# MRCS-CMRI-32-Line-stall-motor-adapter.net
KiCad netlist of a schematic drawn in EAGLE
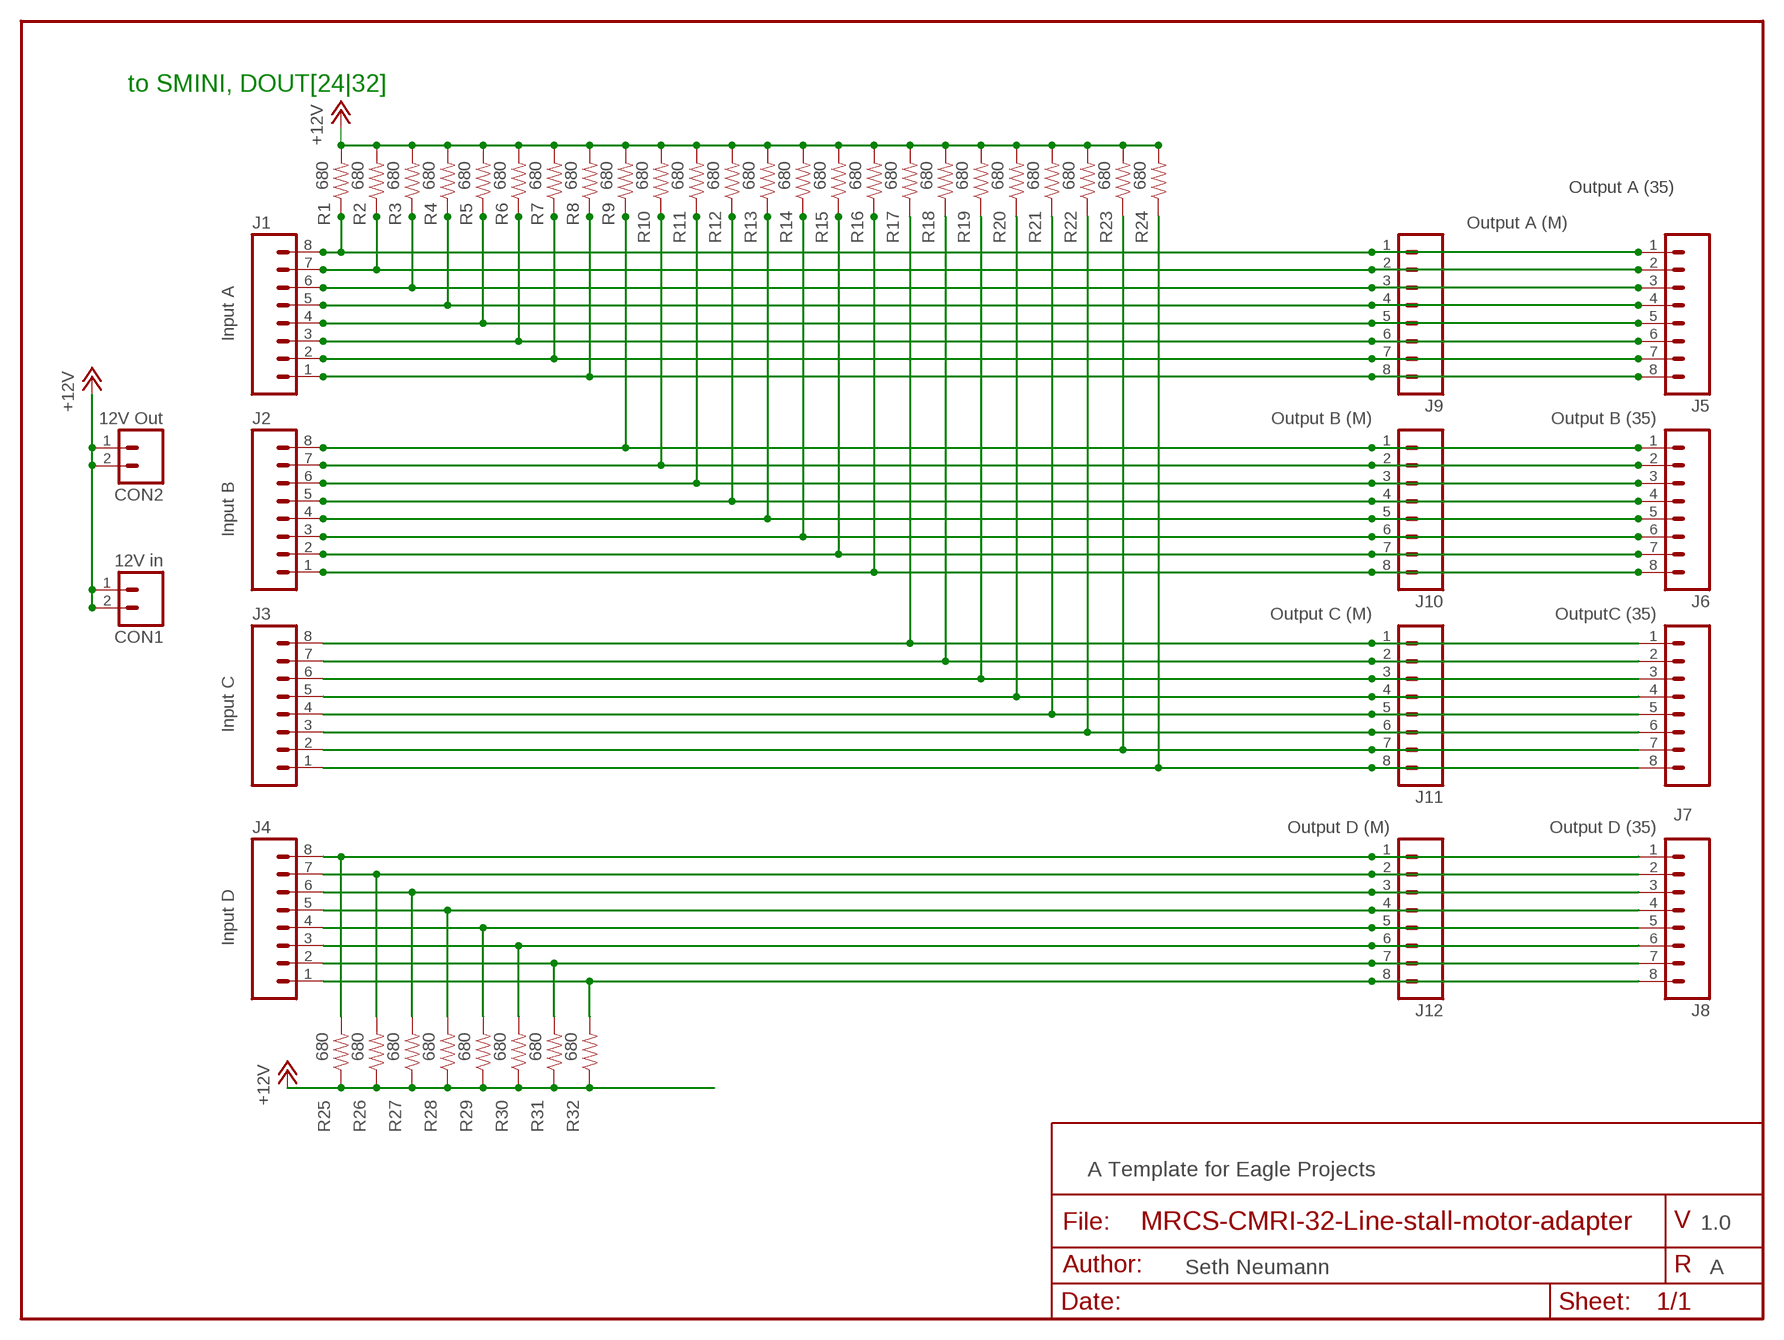
[diagram p0: schematic, sheet 1]

(export (version "E")
  (design (tool "Eeschema 10.0.6"))
  (components
    (comp (ref "CON1")
      (value "12V in")
      (footprint "eagle-import:SCREWTERMINAL-5MM-2")
      (libsource (lib "eagle-import") (part "CONNECTOR-M025MM-LOCK"))
    )
    (comp (ref "CON2")
      (value "12V Out")
      (footprint "eagle-import:SCREWTERMINAL-5MM-2")
      (libsource (lib "eagle-import") (part "CONNECTOR-M025MM-LOCK"))
    )
    (comp (ref "J1")
      (value "Input A")
      (footprint "eagle-import:KK-156-8-F")
      (libsource (lib "eagle-import") (part "CONNECTOR-M081.56-F"))
    )
    (comp (ref "J2")
      (value "Input B")
      (footprint "eagle-import:KK-156-8-F")
      (libsource (lib "eagle-import") (part "CONNECTOR-M081.56-F"))
    )
    (comp (ref "J3")
      (value "Input C")
      (footprint "eagle-import:KK-156-8-F")
      (libsource (lib "eagle-import") (part "CONNECTOR-M081.56-F"))
    )
    (comp (ref "J4")
      (value "Input D")
      (footprint "eagle-import:KK-156-8-F")
      (libsource (lib "eagle-import") (part "CONNECTOR-M081.56-F"))
    )
    (comp (ref "J5")
      (value "Output A (35)")
      (footprint "eagle-import:SCREWTERMINAL-3.5MM-8")
      (libsource (lib "eagle-import") (part "CONNECTOR-M083.5MM-8"))
    )
    (comp (ref "J6")
      (value "Output B (35)")
      (footprint "eagle-import:SCREWTERMINAL-3.5MM-8")
      (libsource (lib "eagle-import") (part "CONNECTOR-M083.5MM-8"))
    )
    (comp (ref "J7")
      (value "OutputC (35)")
      (footprint "eagle-import:SCREWTERMINAL-3.5MM-8")
      (libsource (lib "eagle-import") (part "CONNECTOR-M083.5MM-8"))
    )
    (comp (ref "J8")
      (value "Output D (35)")
      (footprint "eagle-import:SCREWTERMINAL-3.5MM-8")
      (libsource (lib "eagle-import") (part "CONNECTOR-M083.5MM-8"))
    )
    (comp (ref "J9")
      (value "Output A (M)")
      (footprint "eagle-import:KK-156-8-F")
      (libsource (lib "eagle-import") (part "CONNECTOR-M081.56-F"))
    )
    (comp (ref "J10")
      (value "Output B (M)")
      (footprint "eagle-import:KK-156-8-F")
      (libsource (lib "eagle-import") (part "CONNECTOR-M081.56-F"))
    )
    (comp (ref "J11")
      (value "Output C (M)")
      (footprint "eagle-import:KK-156-8-F")
      (libsource (lib "eagle-import") (part "CONNECTOR-M081.56-F"))
    )
    (comp (ref "J12")
      (value "Output D (M)")
      (footprint "eagle-import:KK-156-8-F")
      (libsource (lib "eagle-import") (part "CONNECTOR-M081.56-F"))
    )
    (comp (ref "R1")
      (value "680")
      (footprint "eagle-import:AXIAL-0.5")
      (libsource (lib "eagle-import") (part "RESISTORPTH-1/2W"))
    )
    (comp (ref "R2")
      (value "680")
      (footprint "eagle-import:AXIAL-0.5")
      (libsource (lib "eagle-import") (part "RESISTORPTH-1/2W"))
    )
    (comp (ref "R3")
      (value "680")
      (footprint "eagle-import:AXIAL-0.5")
      (libsource (lib "eagle-import") (part "RESISTORPTH-1/2W"))
    )
    (comp (ref "R4")
      (value "680")
      (footprint "eagle-import:AXIAL-0.5")
      (libsource (lib "eagle-import") (part "RESISTORPTH-1/2W"))
    )
    (comp (ref "R5")
      (value "680")
      (footprint "eagle-import:AXIAL-0.5")
      (libsource (lib "eagle-import") (part "RESISTORPTH-1/2W"))
    )
    (comp (ref "R6")
      (value "680")
      (footprint "eagle-import:AXIAL-0.5")
      (libsource (lib "eagle-import") (part "RESISTORPTH-1/2W"))
    )
    (comp (ref "R7")
      (value "680")
      (footprint "eagle-import:AXIAL-0.5")
      (libsource (lib "eagle-import") (part "RESISTORPTH-1/2W"))
    )
    (comp (ref "R8")
      (value "680")
      (footprint "eagle-import:AXIAL-0.5")
      (libsource (lib "eagle-import") (part "RESISTORPTH-1/2W"))
    )
    (comp (ref "R9")
      (value "680")
      (footprint "eagle-import:AXIAL-0.5")
      (libsource (lib "eagle-import") (part "RESISTORPTH-1/2W"))
    )
    (comp (ref "R10")
      (value "680")
      (footprint "eagle-import:AXIAL-0.5")
      (libsource (lib "eagle-import") (part "RESISTORPTH-1/2W"))
    )
    (comp (ref "R11")
      (value "680")
      (footprint "eagle-import:AXIAL-0.5")
      (libsource (lib "eagle-import") (part "RESISTORPTH-1/2W"))
    )
    (comp (ref "R12")
      (value "680")
      (footprint "eagle-import:AXIAL-0.5")
      (libsource (lib "eagle-import") (part "RESISTORPTH-1/2W"))
    )
    (comp (ref "R13")
      (value "680")
      (footprint "eagle-import:AXIAL-0.5")
      (libsource (lib "eagle-import") (part "RESISTORPTH-1/2W"))
    )
    (comp (ref "R14")
      (value "680")
      (footprint "eagle-import:AXIAL-0.5")
      (libsource (lib "eagle-import") (part "RESISTORPTH-1/2W"))
    )
    (comp (ref "R15")
      (value "680")
      (footprint "eagle-import:AXIAL-0.5")
      (libsource (lib "eagle-import") (part "RESISTORPTH-1/2W"))
    )
    (comp (ref "R16")
      (value "680")
      (footprint "eagle-import:AXIAL-0.5")
      (libsource (lib "eagle-import") (part "RESISTORPTH-1/2W"))
    )
    (comp (ref "R17")
      (value "680")
      (footprint "eagle-import:AXIAL-0.5")
      (libsource (lib "eagle-import") (part "RESISTORPTH-1/2W"))
    )
    (comp (ref "R18")
      (value "680")
      (footprint "eagle-import:AXIAL-0.5")
      (libsource (lib "eagle-import") (part "RESISTORPTH-1/2W"))
    )
    (comp (ref "R19")
      (value "680")
      (footprint "eagle-import:AXIAL-0.5")
      (libsource (lib "eagle-import") (part "RESISTORPTH-1/2W"))
    )
    (comp (ref "R20")
      (value "680")
      (footprint "eagle-import:AXIAL-0.5")
      (libsource (lib "eagle-import") (part "RESISTORPTH-1/2W"))
    )
    (comp (ref "R21")
      (value "680")
      (footprint "eagle-import:AXIAL-0.5")
      (libsource (lib "eagle-import") (part "RESISTORPTH-1/2W"))
    )
    (comp (ref "R22")
      (value "680")
      (footprint "eagle-import:AXIAL-0.5")
      (libsource (lib "eagle-import") (part "RESISTORPTH-1/2W"))
    )
    (comp (ref "R23")
      (value "680")
      (footprint "eagle-import:AXIAL-0.5")
      (libsource (lib "eagle-import") (part "RESISTORPTH-1/2W"))
    )
    (comp (ref "R24")
      (value "680")
      (footprint "eagle-import:AXIAL-0.5")
      (libsource (lib "eagle-import") (part "RESISTORPTH-1/2W"))
    )
    (comp (ref "R25")
      (value "680")
      (footprint "eagle-import:AXIAL-0.5")
      (libsource (lib "eagle-import") (part "RESISTORPTH-1/2W"))
    )
    (comp (ref "R26")
      (value "680")
      (footprint "eagle-import:AXIAL-0.5")
      (libsource (lib "eagle-import") (part "RESISTORPTH-1/2W"))
    )
    (comp (ref "R27")
      (value "680")
      (footprint "eagle-import:AXIAL-0.5")
      (libsource (lib "eagle-import") (part "RESISTORPTH-1/2W"))
    )
    (comp (ref "R28")
      (value "680")
      (footprint "eagle-import:AXIAL-0.5")
      (libsource (lib "eagle-import") (part "RESISTORPTH-1/2W"))
    )
    (comp (ref "R29")
      (value "680")
      (footprint "eagle-import:AXIAL-0.5")
      (libsource (lib "eagle-import") (part "RESISTORPTH-1/2W"))
    )
    (comp (ref "R30")
      (value "680")
      (footprint "eagle-import:AXIAL-0.5")
      (libsource (lib "eagle-import") (part "RESISTORPTH-1/2W"))
    )
    (comp (ref "R31")
      (value "680")
      (footprint "eagle-import:AXIAL-0.5")
      (libsource (lib "eagle-import") (part "RESISTORPTH-1/2W"))
    )
    (comp (ref "R32")
      (value "680")
      (footprint "eagle-import:AXIAL-0.5")
      (libsource (lib "eagle-import") (part "RESISTORPTH-1/2W"))
    )
  )
  (nets
    (net (code "1") (name "+12V") (class "Default")
      (node (ref "CON1") (pin "1") (pinfunction "A_1") (pintype "passive"))
      (node (ref "CON1") (pin "2") (pinfunction "B_2") (pintype "passive"))
      (node (ref "CON2") (pin "1") (pinfunction "A_1") (pintype "passive"))
      (node (ref "CON2") (pin "2") (pinfunction "B_2") (pintype "passive"))
      (node (ref "R1") (pin "P$2") (pinfunction "2_P$2") (pintype "passive"))
      (node (ref "R10") (pin "P$2") (pinfunction "2_P$2") (pintype "passive"))
      (node (ref "R11") (pin "P$2") (pinfunction "2_P$2") (pintype "passive"))
      (node (ref "R12") (pin "P$2") (pinfunction "2_P$2") (pintype "passive"))
      (node (ref "R13") (pin "P$2") (pinfunction "2_P$2") (pintype "passive"))
      (node (ref "R14") (pin "P$2") (pinfunction "2_P$2") (pintype "passive"))
      (node (ref "R15") (pin "P$2") (pinfunction "2_P$2") (pintype "passive"))
      (node (ref "R16") (pin "P$2") (pinfunction "2_P$2") (pintype "passive"))
      (node (ref "R17") (pin "P$2") (pinfunction "2_P$2") (pintype "passive"))
      (node (ref "R18") (pin "P$2") (pinfunction "2_P$2") (pintype "passive"))
      (node (ref "R19") (pin "P$2") (pinfunction "2_P$2") (pintype "passive"))
      (node (ref "R2") (pin "P$2") (pinfunction "2_P$2") (pintype "passive"))
      (node (ref "R20") (pin "P$2") (pinfunction "2_P$2") (pintype "passive"))
      (node (ref "R21") (pin "P$2") (pinfunction "2_P$2") (pintype "passive"))
      (node (ref "R22") (pin "P$2") (pinfunction "2_P$2") (pintype "passive"))
      (node (ref "R23") (pin "P$2") (pinfunction "2_P$2") (pintype "passive"))
      (node (ref "R24") (pin "P$2") (pinfunction "2_P$2") (pintype "passive"))
      (node (ref "R25") (pin "P$1") (pinfunction "1_P$1") (pintype "passive"))
      (node (ref "R26") (pin "P$1") (pinfunction "1_P$1") (pintype "passive"))
      (node (ref "R27") (pin "P$1") (pinfunction "1_P$1") (pintype "passive"))
      (node (ref "R28") (pin "P$1") (pinfunction "1_P$1") (pintype "passive"))
      (node (ref "R29") (pin "P$1") (pinfunction "1_P$1") (pintype "passive"))
      (node (ref "R3") (pin "P$2") (pinfunction "2_P$2") (pintype "passive"))
      (node (ref "R30") (pin "P$1") (pinfunction "1_P$1") (pintype "passive"))
      (node (ref "R31") (pin "P$1") (pinfunction "1_P$1") (pintype "passive"))
      (node (ref "R32") (pin "P$1") (pinfunction "1_P$1") (pintype "passive"))
      (node (ref "R4") (pin "P$2") (pinfunction "2_P$2") (pintype "passive"))
      (node (ref "R5") (pin "P$2") (pinfunction "2_P$2") (pintype "passive"))
      (node (ref "R6") (pin "P$2") (pinfunction "2_P$2") (pintype "passive"))
      (node (ref "R7") (pin "P$2") (pinfunction "2_P$2") (pintype "passive"))
      (node (ref "R8") (pin "P$2") (pinfunction "2_P$2") (pintype "passive"))
      (node (ref "R9") (pin "P$2") (pinfunction "2_P$2") (pintype "passive"))
    )
    (net (code "2") (name "Net-(R1-1)") (class "Default")
      (node (ref "J1") (pin "8") (pinfunction "8_8") (pintype "passive"))
      (node (ref "J5") (pin "1") (pinfunction "1_1") (pintype "passive"))
      (node (ref "J9") (pin "1") (pinfunction "1_1") (pintype "passive"))
      (node (ref "R1") (pin "P$1") (pinfunction "1_P$1") (pintype "passive"))
    )
    (net (code "3") (name "Net-(R2-1)") (class "Default")
      (node (ref "J1") (pin "7") (pinfunction "7_7") (pintype "passive"))
      (node (ref "J5") (pin "2") (pinfunction "2_2") (pintype "passive"))
      (node (ref "J9") (pin "2") (pinfunction "2_2") (pintype "passive"))
      (node (ref "R2") (pin "P$1") (pinfunction "1_P$1") (pintype "passive"))
    )
    (net (code "4") (name "Net-(R3-1)") (class "Default")
      (node (ref "J1") (pin "6") (pinfunction "6_6") (pintype "passive"))
      (node (ref "J5") (pin "3") (pinfunction "3_3") (pintype "passive"))
      (node (ref "J9") (pin "3") (pinfunction "3_3") (pintype "passive"))
      (node (ref "R3") (pin "P$1") (pinfunction "1_P$1") (pintype "passive"))
    )
    (net (code "5") (name "Net-(R4-1)") (class "Default")
      (node (ref "J1") (pin "5") (pinfunction "5_5") (pintype "passive"))
      (node (ref "J5") (pin "4") (pinfunction "4_4") (pintype "passive"))
      (node (ref "J9") (pin "4") (pinfunction "4_4") (pintype "passive"))
      (node (ref "R4") (pin "P$1") (pinfunction "1_P$1") (pintype "passive"))
    )
    (net (code "6") (name "Net-(R5-1)") (class "Default")
      (node (ref "J1") (pin "4") (pinfunction "4_4") (pintype "passive"))
      (node (ref "J5") (pin "5") (pinfunction "5_5") (pintype "passive"))
      (node (ref "J9") (pin "5") (pinfunction "5_5") (pintype "passive"))
      (node (ref "R5") (pin "P$1") (pinfunction "1_P$1") (pintype "passive"))
    )
    (net (code "7") (name "Net-(R6-1)") (class "Default")
      (node (ref "J1") (pin "3") (pinfunction "3_3") (pintype "passive"))
      (node (ref "J5") (pin "6") (pinfunction "6_6") (pintype "passive"))
      (node (ref "J9") (pin "6") (pinfunction "6_6") (pintype "passive"))
      (node (ref "R6") (pin "P$1") (pinfunction "1_P$1") (pintype "passive"))
    )
    (net (code "8") (name "Net-(R7-1)") (class "Default")
      (node (ref "J1") (pin "2") (pinfunction "2_2") (pintype "passive"))
      (node (ref "J5") (pin "7") (pinfunction "7_7") (pintype "passive"))
      (node (ref "J9") (pin "7") (pinfunction "7_7") (pintype "passive"))
      (node (ref "R7") (pin "P$1") (pinfunction "1_P$1") (pintype "passive"))
    )
    (net (code "9") (name "Net-(R8-1)") (class "Default")
      (node (ref "J1") (pin "1") (pinfunction "1_1") (pintype "passive"))
      (node (ref "J5") (pin "8") (pinfunction "8_8") (pintype "passive"))
      (node (ref "J9") (pin "8") (pinfunction "8_8") (pintype "passive"))
      (node (ref "R8") (pin "P$1") (pinfunction "1_P$1") (pintype "passive"))
    )
    (net (code "10") (name "Net-(R9-1)") (class "Default")
      (node (ref "J10") (pin "1") (pinfunction "1_1") (pintype "passive"))
      (node (ref "J2") (pin "8") (pinfunction "8_8") (pintype "passive"))
      (node (ref "J6") (pin "1") (pinfunction "1_1") (pintype "passive"))
      (node (ref "R9") (pin "P$1") (pinfunction "1_P$1") (pintype "passive"))
    )
    (net (code "11") (name "Net-(R10-1)") (class "Default")
      (node (ref "J10") (pin "2") (pinfunction "2_2") (pintype "passive"))
      (node (ref "J2") (pin "7") (pinfunction "7_7") (pintype "passive"))
      (node (ref "J6") (pin "2") (pinfunction "2_2") (pintype "passive"))
      (node (ref "R10") (pin "P$1") (pinfunction "1_P$1") (pintype "passive"))
    )
    (net (code "12") (name "Net-(R11-1)") (class "Default")
      (node (ref "J10") (pin "3") (pinfunction "3_3") (pintype "passive"))
      (node (ref "J2") (pin "6") (pinfunction "6_6") (pintype "passive"))
      (node (ref "J6") (pin "3") (pinfunction "3_3") (pintype "passive"))
      (node (ref "R11") (pin "P$1") (pinfunction "1_P$1") (pintype "passive"))
    )
    (net (code "13") (name "Net-(R12-1)") (class "Default")
      (node (ref "J10") (pin "4") (pinfunction "4_4") (pintype "passive"))
      (node (ref "J2") (pin "5") (pinfunction "5_5") (pintype "passive"))
      (node (ref "J6") (pin "4") (pinfunction "4_4") (pintype "passive"))
      (node (ref "R12") (pin "P$1") (pinfunction "1_P$1") (pintype "passive"))
    )
    (net (code "14") (name "Net-(R13-1)") (class "Default")
      (node (ref "J10") (pin "5") (pinfunction "5_5") (pintype "passive"))
      (node (ref "J2") (pin "4") (pinfunction "4_4") (pintype "passive"))
      (node (ref "J6") (pin "5") (pinfunction "5_5") (pintype "passive"))
      (node (ref "R13") (pin "P$1") (pinfunction "1_P$1") (pintype "passive"))
    )
    (net (code "15") (name "Net-(R14-1)") (class "Default")
      (node (ref "J10") (pin "6") (pinfunction "6_6") (pintype "passive"))
      (node (ref "J2") (pin "3") (pinfunction "3_3") (pintype "passive"))
      (node (ref "J6") (pin "6") (pinfunction "6_6") (pintype "passive"))
      (node (ref "R14") (pin "P$1") (pinfunction "1_P$1") (pintype "passive"))
    )
    (net (code "16") (name "Net-(R15-1)") (class "Default")
      (node (ref "J10") (pin "7") (pinfunction "7_7") (pintype "passive"))
      (node (ref "J2") (pin "2") (pinfunction "2_2") (pintype "passive"))
      (node (ref "J6") (pin "7") (pinfunction "7_7") (pintype "passive"))
      (node (ref "R15") (pin "P$1") (pinfunction "1_P$1") (pintype "passive"))
    )
    (net (code "17") (name "Net-(R16-1)") (class "Default")
      (node (ref "J10") (pin "8") (pinfunction "8_8") (pintype "passive"))
      (node (ref "J2") (pin "1") (pinfunction "1_1") (pintype "passive"))
      (node (ref "J6") (pin "8") (pinfunction "8_8") (pintype "passive"))
      (node (ref "R16") (pin "P$1") (pinfunction "1_P$1") (pintype "passive"))
    )
    (net (code "18") (name "Net-(R17-1)") (class "Default")
      (node (ref "J11") (pin "1") (pinfunction "1_1") (pintype "passive"))
      (node (ref "J3") (pin "8") (pinfunction "8_8") (pintype "passive"))
      (node (ref "J7") (pin "1") (pinfunction "1_1") (pintype "passive"))
      (node (ref "R17") (pin "P$1") (pinfunction "1_P$1") (pintype "passive"))
    )
    (net (code "19") (name "Net-(R18-1)") (class "Default")
      (node (ref "J11") (pin "2") (pinfunction "2_2") (pintype "passive"))
      (node (ref "J3") (pin "7") (pinfunction "7_7") (pintype "passive"))
      (node (ref "J7") (pin "2") (pinfunction "2_2") (pintype "passive"))
      (node (ref "R18") (pin "P$1") (pinfunction "1_P$1") (pintype "passive"))
    )
    (net (code "20") (name "Net-(R19-1)") (class "Default")
      (node (ref "J11") (pin "3") (pinfunction "3_3") (pintype "passive"))
      (node (ref "J3") (pin "6") (pinfunction "6_6") (pintype "passive"))
      (node (ref "J7") (pin "3") (pinfunction "3_3") (pintype "passive"))
      (node (ref "R19") (pin "P$1") (pinfunction "1_P$1") (pintype "passive"))
    )
    (net (code "21") (name "Net-(R20-1)") (class "Default")
      (node (ref "J11") (pin "4") (pinfunction "4_4") (pintype "passive"))
      (node (ref "J3") (pin "5") (pinfunction "5_5") (pintype "passive"))
      (node (ref "J7") (pin "4") (pinfunction "4_4") (pintype "passive"))
      (node (ref "R20") (pin "P$1") (pinfunction "1_P$1") (pintype "passive"))
    )
    (net (code "22") (name "Net-(R21-1)") (class "Default")
      (node (ref "J11") (pin "5") (pinfunction "5_5") (pintype "passive"))
      (node (ref "J3") (pin "4") (pinfunction "4_4") (pintype "passive"))
      (node (ref "J7") (pin "5") (pinfunction "5_5") (pintype "passive"))
      (node (ref "R21") (pin "P$1") (pinfunction "1_P$1") (pintype "passive"))
    )
    (net (code "23") (name "Net-(R22-1)") (class "Default")
      (node (ref "J11") (pin "6") (pinfunction "6_6") (pintype "passive"))
      (node (ref "J3") (pin "3") (pinfunction "3_3") (pintype "passive"))
      (node (ref "J7") (pin "6") (pinfunction "6_6") (pintype "passive"))
      (node (ref "R22") (pin "P$1") (pinfunction "1_P$1") (pintype "passive"))
    )
    (net (code "24") (name "Net-(R23-1)") (class "Default")
      (node (ref "J11") (pin "7") (pinfunction "7_7") (pintype "passive"))
      (node (ref "J3") (pin "2") (pinfunction "2_2") (pintype "passive"))
      (node (ref "J7") (pin "7") (pinfunction "7_7") (pintype "passive"))
      (node (ref "R23") (pin "P$1") (pinfunction "1_P$1") (pintype "passive"))
    )
    (net (code "25") (name "Net-(R24-1)") (class "Default")
      (node (ref "J11") (pin "8") (pinfunction "8_8") (pintype "passive"))
      (node (ref "J3") (pin "1") (pinfunction "1_1") (pintype "passive"))
      (node (ref "J7") (pin "8") (pinfunction "8_8") (pintype "passive"))
      (node (ref "R24") (pin "P$1") (pinfunction "1_P$1") (pintype "passive"))
    )
    (net (code "26") (name "Net-(R25-2)") (class "Default")
      (node (ref "J12") (pin "1") (pinfunction "1_1") (pintype "passive"))
      (node (ref "J4") (pin "8") (pinfunction "8_8") (pintype "passive"))
      (node (ref "J8") (pin "1") (pinfunction "1_1") (pintype "passive"))
      (node (ref "R25") (pin "P$2") (pinfunction "2_P$2") (pintype "passive"))
    )
    (net (code "27") (name "Net-(R26-2)") (class "Default")
      (node (ref "J12") (pin "2") (pinfunction "2_2") (pintype "passive"))
      (node (ref "J4") (pin "7") (pinfunction "7_7") (pintype "passive"))
      (node (ref "J8") (pin "2") (pinfunction "2_2") (pintype "passive"))
      (node (ref "R26") (pin "P$2") (pinfunction "2_P$2") (pintype "passive"))
    )
    (net (code "28") (name "Net-(R27-2)") (class "Default")
      (node (ref "J12") (pin "3") (pinfunction "3_3") (pintype "passive"))
      (node (ref "J4") (pin "6") (pinfunction "6_6") (pintype "passive"))
      (node (ref "J8") (pin "3") (pinfunction "3_3") (pintype "passive"))
      (node (ref "R27") (pin "P$2") (pinfunction "2_P$2") (pintype "passive"))
    )
    (net (code "29") (name "Net-(R28-2)") (class "Default")
      (node (ref "J12") (pin "4") (pinfunction "4_4") (pintype "passive"))
      (node (ref "J4") (pin "5") (pinfunction "5_5") (pintype "passive"))
      (node (ref "J8") (pin "4") (pinfunction "4_4") (pintype "passive"))
      (node (ref "R28") (pin "P$2") (pinfunction "2_P$2") (pintype "passive"))
    )
    (net (code "30") (name "Net-(R29-2)") (class "Default")
      (node (ref "J12") (pin "5") (pinfunction "5_5") (pintype "passive"))
      (node (ref "J4") (pin "4") (pinfunction "4_4") (pintype "passive"))
      (node (ref "J8") (pin "5") (pinfunction "5_5") (pintype "passive"))
      (node (ref "R29") (pin "P$2") (pinfunction "2_P$2") (pintype "passive"))
    )
    (net (code "31") (name "Net-(R30-2)") (class "Default")
      (node (ref "J12") (pin "6") (pinfunction "6_6") (pintype "passive"))
      (node (ref "J4") (pin "3") (pinfunction "3_3") (pintype "passive"))
      (node (ref "J8") (pin "6") (pinfunction "6_6") (pintype "passive"))
      (node (ref "R30") (pin "P$2") (pinfunction "2_P$2") (pintype "passive"))
    )
    (net (code "32") (name "Net-(R31-2)") (class "Default")
      (node (ref "J12") (pin "7") (pinfunction "7_7") (pintype "passive"))
      (node (ref "J4") (pin "2") (pinfunction "2_2") (pintype "passive"))
      (node (ref "J8") (pin "7") (pinfunction "7_7") (pintype "passive"))
      (node (ref "R31") (pin "P$2") (pinfunction "2_P$2") (pintype "passive"))
    )
    (net (code "33") (name "Net-(R32-2)") (class "Default")
      (node (ref "J12") (pin "8") (pinfunction "8_8") (pintype "passive"))
      (node (ref "J4") (pin "1") (pinfunction "1_1") (pintype "passive"))
      (node (ref "J8") (pin "8") (pinfunction "8_8") (pintype "passive"))
      (node (ref "R32") (pin "P$2") (pinfunction "2_P$2") (pintype "passive"))
    )
  )
)
